# FM-Superregenerative-Receiver-2.net
KiCad netlist of a schematic drawn in EAGLE
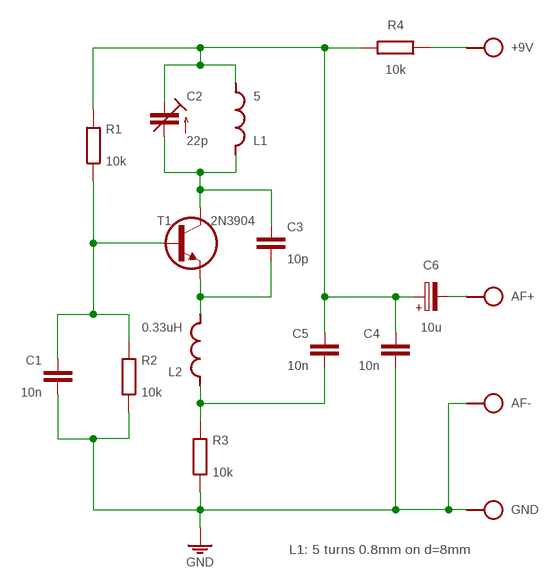
[diagram p0: schematic, sheet 1]

(export (version "E")
  (design (tool "Eeschema 10.0.6"))
  (components
    (comp (ref "+9V")
      (value "SPAD")
      (footprint "eagle-import:SPAD")
      (libsource (lib "eagle-import") (part "SPAD"))
    )
    (comp (ref "AF+")
      (value "SPAD")
      (footprint "eagle-import:SPAD")
      (libsource (lib "eagle-import") (part "SPAD"))
    )
    (comp (ref "AF-")
      (value "SPAD")
      (footprint "eagle-import:SPAD")
      (libsource (lib "eagle-import") (part "SPAD"))
    )
    (comp (ref "C1")
      (value "10n")
      (footprint "eagle-import:C050-020X036_V")
      (libsource (lib "eagle-import") (part "C050-020X036/V"))
    )
    (comp (ref "C2")
      (value "22p")
      (footprint "eagle-import:TRIM-2222-808")
      (libsource (lib "eagle-import") (part "C-TR-PH20127"))
    )
    (comp (ref "C3")
      (value "10p")
      (footprint "eagle-import:C050-020X036_V")
      (libsource (lib "eagle-import") (part "C050-020X036/V"))
    )
    (comp (ref "C4")
      (value "10n")
      (footprint "eagle-import:C050-020X036_V")
      (libsource (lib "eagle-import") (part "C050-020X036/V"))
    )
    (comp (ref "C5")
      (value "10n")
      (footprint "eagle-import:C050-020X036_V")
      (libsource (lib "eagle-import") (part "C050-020X036/V"))
    )
    (comp (ref "C6")
      (value "10u")
      (footprint "eagle-import:E2,5-3")
      (libsource (lib "eagle-import") (part "CPOLE2,5-3"))
    )
    (comp (ref "GND")
      (value "SPAD")
      (footprint "eagle-import:SPAD")
      (libsource (lib "eagle-import") (part "SPAD"))
    )
    (comp (ref "L1")
      (value "5")
      (footprint "eagle-import:L-04-5_5V-X")
      (libsource (lib "eagle-import") (part "L-SHORTL-04-5/5V-X"))
    )
    (comp (ref "L2")
      (value "0.33uH")
      (footprint "eagle-import:L-02_7V")
      (libsource (lib "eagle-import") (part "L-SHORT02/7V"))
    )
    (comp (ref "R1")
      (value "10k")
      (footprint "eagle-import:0204_10")
      (libsource (lib "eagle-import") (part "R0204/10"))
    )
    (comp (ref "R2")
      (value "10k")
      (footprint "eagle-import:0204_10")
      (libsource (lib "eagle-import") (part "R0204/10"))
    )
    (comp (ref "R3")
      (value "10k")
      (footprint "eagle-import:0204_10")
      (libsource (lib "eagle-import") (part "R0204/10"))
    )
    (comp (ref "R4")
      (value "10k")
      (footprint "eagle-import:0204_7")
      (libsource (lib "eagle-import") (part "R0204/7"))
    )
    (comp (ref "T1")
      (value "2N3904")
      (footprint "eagle-import:TO92")
      (libsource (lib "eagle-import") (part "2N3904"))
    )
  )
  (nets
    (net (code "1") (name "GND") (class "Default")
      (node (ref "AF-") (pin "1") (pinfunction "P$1_1") (pintype "passive"))
      (node (ref "C1") (pin "2") (pinfunction "2_2") (pintype "passive"))
      (node (ref "C4") (pin "2") (pinfunction "2_2") (pintype "passive"))
      (node (ref "GND") (pin "1") (pinfunction "P$1_1") (pintype "passive"))
      (node (ref "R2") (pin "1") (pinfunction "1_1") (pintype "passive"))
      (node (ref "R3") (pin "1") (pinfunction "1_1") (pintype "passive"))
    )
    (net (code "2") (name "Net-(+9V-P$1)") (class "Default")
      (node (ref "+9V") (pin "1") (pinfunction "P$1_1") (pintype "passive"))
      (node (ref "R4") (pin "1") (pinfunction "1_1") (pintype "passive"))
    )
    (net (code "3") (name "Net-(AF+-P$1)") (class "Default")
      (node (ref "AF+") (pin "1") (pinfunction "P$1_1") (pintype "passive"))
      (node (ref "C6") (pin "-") (pinfunction "-_-") (pintype "passive"))
    )
    (net (code "4") (name "Net-(C2-A)") (class "Default")
      (node (ref "C2") (pin "2") (pinfunction "A_2") (pintype "passive"))
      (node (ref "C3") (pin "1") (pinfunction "1_1") (pintype "passive"))
      (node (ref "L1") (pin "2") (pinfunction "2_2") (pintype "passive"))
      (node (ref "T1") (pin "3") (pinfunction "C_3") (pintype "passive"))
    )
    (net (code "5") (name "Net-(C2-E-Pad1)") (class "Default")
      (node (ref "C2") (pin "1") (pinfunction "E_1") (pintype "passive"))
      (node (ref "C2") (pin "3") (pinfunction "E_3") (pintype "passive"))
      (node (ref "C4") (pin "1") (pinfunction "1_1") (pintype "passive"))
      (node (ref "C5") (pin "1") (pinfunction "1_1") (pintype "passive"))
      (node (ref "C6") (pin "+") (pinfunction "+_+") (pintype "passive"))
      (node (ref "L1") (pin "1") (pinfunction "1_1") (pintype "passive"))
      (node (ref "R1") (pin "2") (pinfunction "2_2") (pintype "passive"))
      (node (ref "R4") (pin "2") (pinfunction "2_2") (pintype "passive"))
    )
    (net (code "6") (name "Net-(C5-Pad2)") (class "Default")
      (node (ref "C5") (pin "2") (pinfunction "2_2") (pintype "passive"))
      (node (ref "L2") (pin "2") (pinfunction "2_2") (pintype "passive"))
      (node (ref "R3") (pin "2") (pinfunction "2_2") (pintype "passive"))
    )
    (net (code "7") (name "Net-(T1-B)") (class "Default")
      (node (ref "C1") (pin "1") (pinfunction "1_1") (pintype "passive"))
      (node (ref "R1") (pin "1") (pinfunction "1_1") (pintype "passive"))
      (node (ref "R2") (pin "2") (pinfunction "2_2") (pintype "passive"))
      (node (ref "T1") (pin "2") (pinfunction "B_2") (pintype "passive"))
    )
    (net (code "8") (name "Net-(T1-E)") (class "Default")
      (node (ref "C3") (pin "2") (pinfunction "2_2") (pintype "passive"))
      (node (ref "L2") (pin "1") (pinfunction "1_1") (pintype "passive"))
      (node (ref "T1") (pin "1") (pinfunction "E_1") (pintype "passive"))
    )
  )
)
